# URC_eZFET_Lite-Headers.net
KiCad netlist of a schematic drawn in Altium Designer
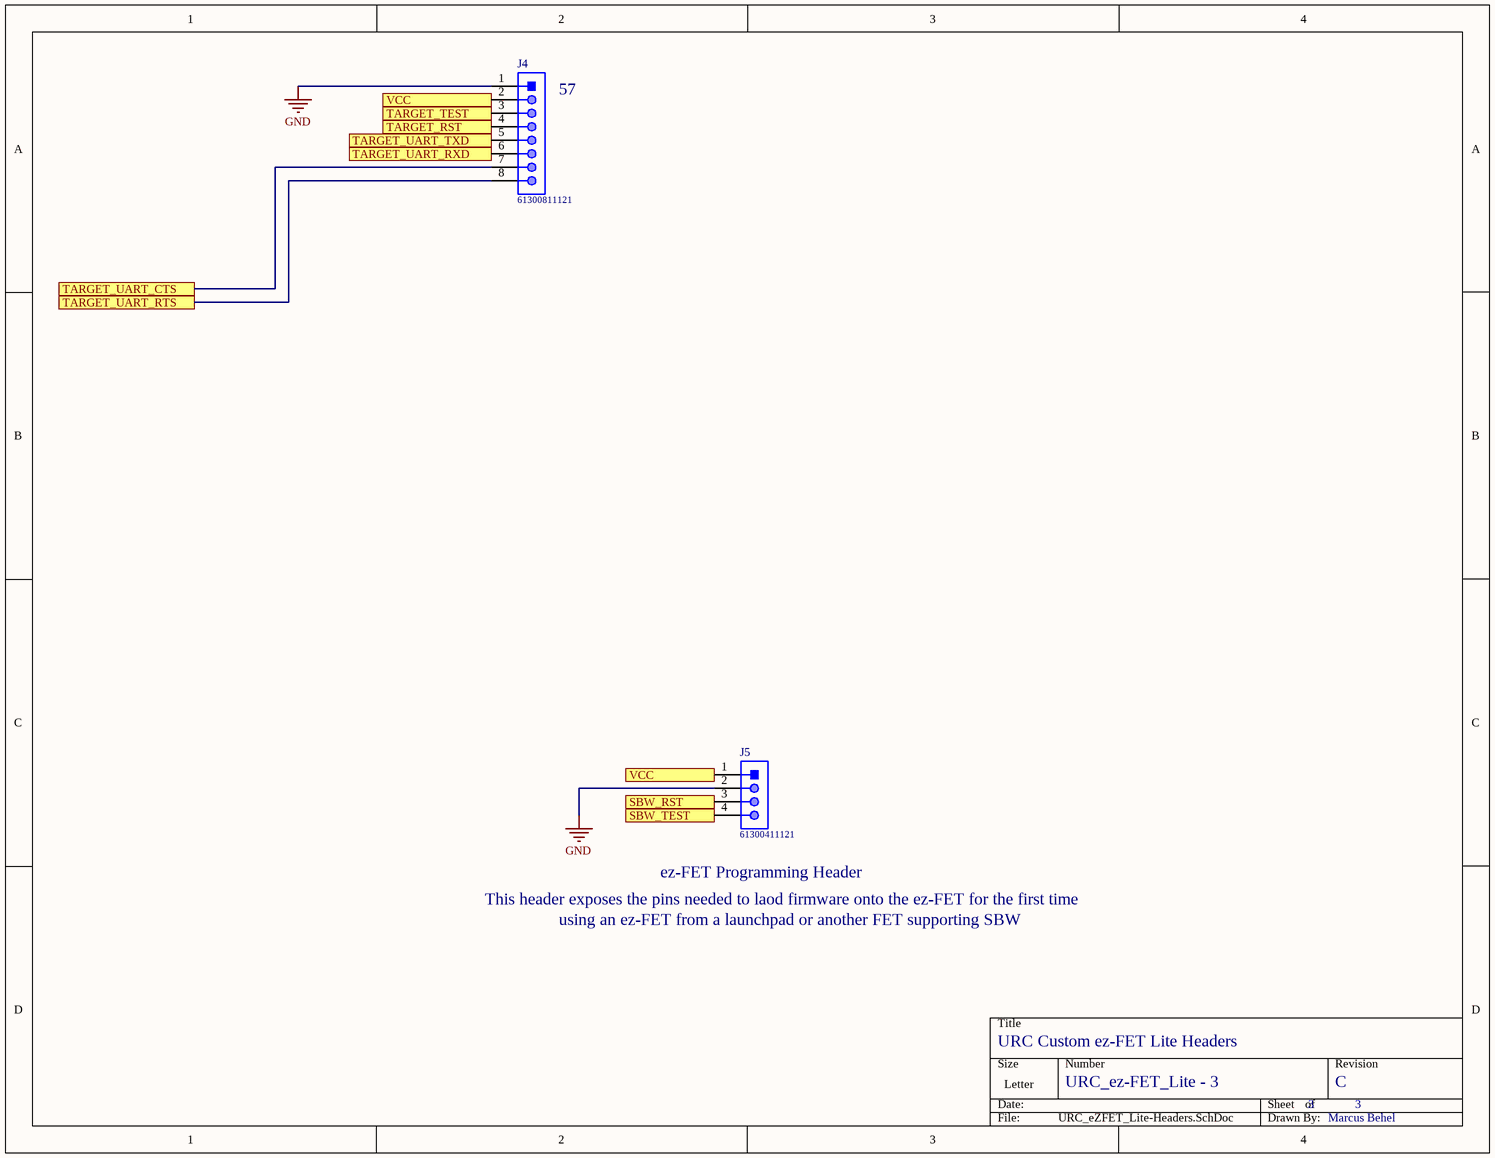
[diagram p0: URC_eZFET_Lite-Headers.SchDoc]

(export (version "E")
  (design (tool "Eeschema 10.0.6"))
  (components
    (comp (ref "J4")
      (value "61300811121")
      (footprint "61300811121")
      (description "THT Vertical Pin Header WR-PHD, Pitch 2.54 mm, Single Row, 8 pins")
      (fields (field (name "MANUFACTURER") "Wurth Elektronik") (field (name "PUBLISHER") "WurthElektronik"))
      (libsource (lib "Altium Content Vault") (part "WE-CN-1P-M-R8"))
    )
    (comp (ref "J5")
      (value "61300411121")
      (footprint "61300411121")
      (description "THT Vertical Pin Header WR-PHD, Pitch 2.54 mm, Single Row, 4 pins")
      (fields (field (name "MANUFACTURER") "Wurth Elektronik") (field (name "PUBLISHER") "WurthElektronik"))
      (libsource (lib "Altium Content Vault") (part "WE-CN-1P-M-R4"))
    )
  )
  (nets
    (net (code "1") (name "/SBW_RST") (class "Default")
      (node (ref "J5") (pin "3") (pinfunction "3_3") (pintype "passive"))
    )
    (net (code "2") (name "/SBW_TEST") (class "Default")
      (node (ref "J5") (pin "4") (pinfunction "4_4") (pintype "passive"))
    )
    (net (code "3") (name "/TARGET_RST") (class "Default")
      (node (ref "J4") (pin "4") (pinfunction "4_4") (pintype "passive"))
    )
    (net (code "4") (name "/TARGET_TEST") (class "Default")
      (node (ref "J4") (pin "3") (pinfunction "3_3") (pintype "passive"))
    )
    (net (code "5") (name "/TARGET_UART_CTS") (class "Default")
      (node (ref "J4") (pin "7") (pinfunction "7_7") (pintype "passive"))
    )
    (net (code "6") (name "/TARGET_UART_RTS") (class "Default")
      (node (ref "J4") (pin "8") (pinfunction "8_8") (pintype "passive"))
    )
    (net (code "7") (name "/TARGET_UART_RXD") (class "Default")
      (node (ref "J4") (pin "6") (pinfunction "6_6") (pintype "passive"))
    )
    (net (code "8") (name "/TARGET_UART_TXD") (class "Default")
      (node (ref "J4") (pin "5") (pinfunction "5_5") (pintype "passive"))
    )
    (net (code "9") (name "/VCC") (class "Default")
      (node (ref "J4") (pin "2") (pinfunction "2_2") (pintype "passive"))
      (node (ref "J5") (pin "1") (pinfunction "1_1") (pintype "passive"))
    )
    (net (code "10") (name "GND") (class "Default")
      (node (ref "J4") (pin "1") (pinfunction "1_1") (pintype "passive"))
      (node (ref "J5") (pin "2") (pinfunction "2_2") (pintype "passive"))
    )
  )
)
